# boost.net
KiCad netlist of a schematic drawn in Altium Designer
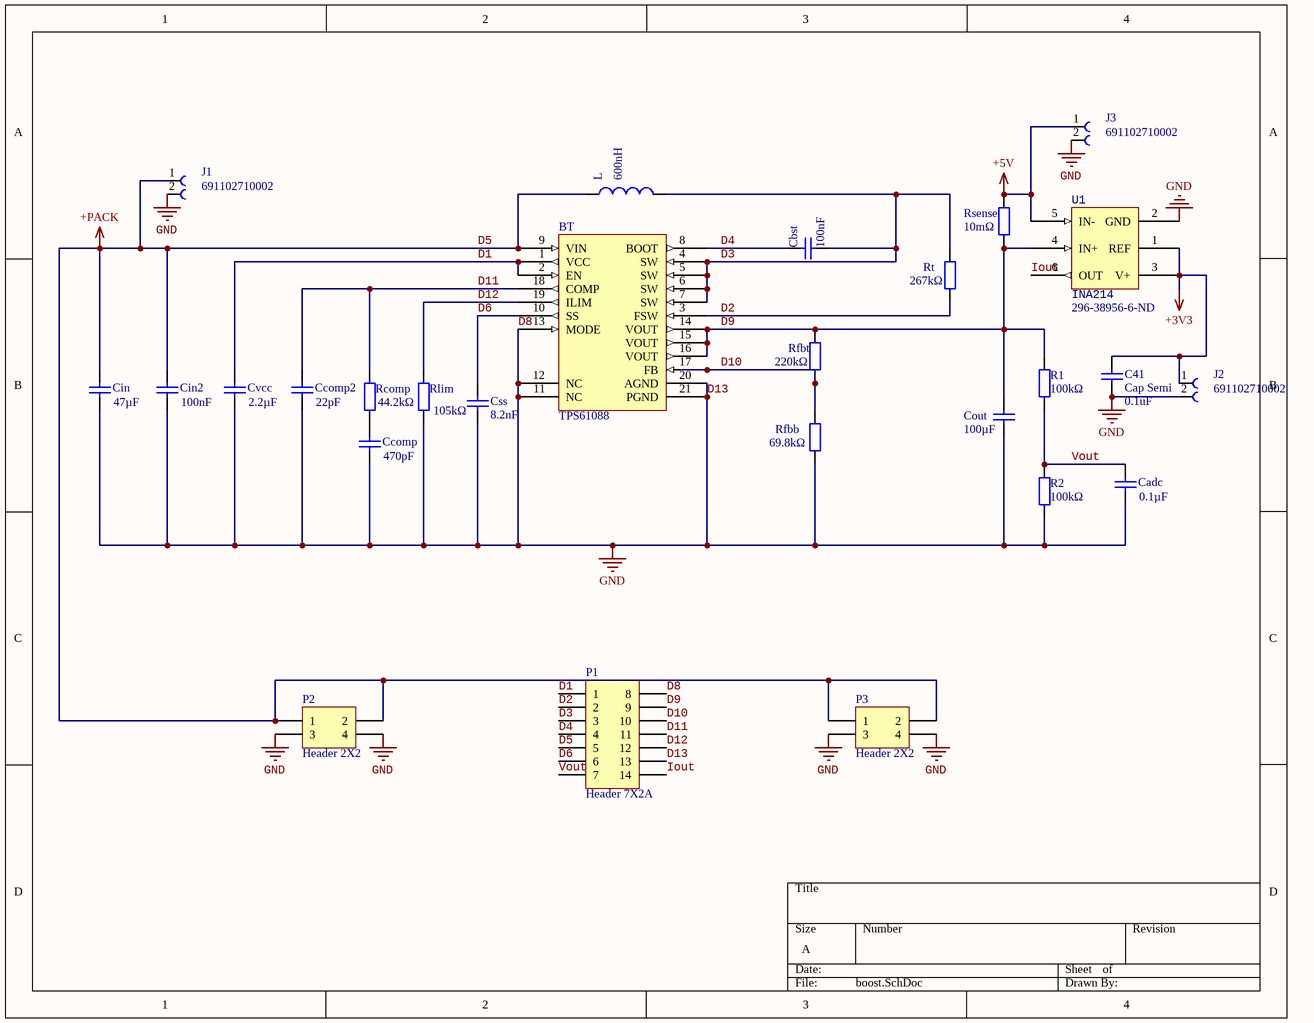
[diagram p0: boost.SchDoc]

(export (version "E")
  (design (tool "Eeschema 10.0.6"))
  (components
    (comp (ref "BT")
      (value "TPS61088")
      (footprint "QFN50P450X350X100-21N")
      (description "Boost converter")
      (libsource (lib "heron-general") (part "TPS61088"))
    )
    (comp (ref "C41")
      (value "Cap Semi")
      (footprint "1608[0603]")
      (description "Capacitor (Semiconductor SIM Model)")
      (fields (field (name "ALTIUM_VALUE") "0.1uF") (field (name "PUBLISHER") "Altium Limited"))
      (libsource (lib "Miscellaneous Devices") (part "Cap Semi"))
    )
    (comp (ref "Cadc")
      (value "0.1µF")
      (footprint "1608[0603]")
      (description "Capacitor")
      (fields (field (name "PUBLISHER") "Altium Limited"))
      (libsource (lib "Miscellaneous Devices") (part "Cap"))
    )
    (comp (ref "Cbst")
      (value "100nF")
      (footprint "1608[0603]")
      (description "Capacitor")
      (fields (field (name "PUBLISHER") "Altium Limited"))
      (libsource (lib "Miscellaneous Devices") (part "Cap"))
    )
    (comp (ref "Ccomp")
      (value "470pF")
      (footprint "1608[0603]")
      (description "Capacitor")
      (fields (field (name "PUBLISHER") "Altium Limited"))
      (libsource (lib "Miscellaneous Devices") (part "Cap"))
    )
    (comp (ref "Ccomp2")
      (value "22pF")
      (footprint "0805")
      (description "Capacitor")
      (fields (field (name "PUBLISHER") "Altium Limited"))
      (libsource (lib "Miscellaneous Devices") (part "Cap"))
    )
    (comp (ref "Cin")
      (value "47µF")
      (footprint "1608[0603]")
      (description "Capacitor")
      (fields (field (name "PUBLISHER") "Altium Limited"))
      (libsource (lib "Miscellaneous Devices") (part "Cap"))
    )
    (comp (ref "Cin2")
      (value "100nF")
      (footprint "1608[0603]")
      (description "Capacitor")
      (fields (field (name "PUBLISHER") "Altium Limited"))
      (libsource (lib "Miscellaneous Devices") (part "Cap"))
    )
    (comp (ref "Cout")
      (value "100µF")
      (footprint "1210")
      (description "Capacitor")
      (fields (field (name "PUBLISHER") "Altium Limited"))
      (libsource (lib "Miscellaneous Devices") (part "Cap"))
    )
    (comp (ref "Css")
      (value "8.2nF")
      (footprint "0805")
      (description "Capacitor")
      (fields (field (name "PUBLISHER") "Altium Limited"))
      (libsource (lib "Miscellaneous Devices") (part "Cap"))
    )
    (comp (ref "Cvcc")
      (value "2.2µF")
      (footprint "0805")
      (description "Capacitor")
      (fields (field (name "PUBLISHER") "Altium Limited"))
      (libsource (lib "Miscellaneous Devices") (part "Cap"))
    )
    (comp (ref "J1")
      (value "691102710002")
      (footprint "691102710002:691102710002")
      (description "102 Series 5mm Pitch Straight, PCB Terminal Block, Through Hole, 2 Way")
      (fields (field (name "MF") "Wurth Electronics"))
      (libsource (lib "691102710002") (part "691102710002"))
    )
    (comp (ref "J2")
      (value "691102710002")
      (footprint "691102710002:691102710002")
      (description "102 Series 5mm Pitch Straight, PCB Terminal Block, Through Hole, 2 Way")
      (fields (field (name "MF") "Wurth Electronics"))
      (libsource (lib "691102710002") (part "691102710002"))
    )
    (comp (ref "J3")
      (value "691102710002")
      (footprint "691102710002:691102710002")
      (description "102 Series 5mm Pitch Straight, PCB Terminal Block, Through Hole, 2 Way")
      (fields (field (name "MF") "Wurth Electronics"))
      (libsource (lib "691102710002") (part "691102710002"))
    )
    (comp (ref "L")
      (value "600nH")
      (footprint "2-SMD")
      (description "Inductor")
      (fields (field (name "PUBLISHER") "Altium Limited"))
      (libsource (lib "Miscellaneous Devices") (part "Inductor"))
    )
    (comp (ref "P1")
      (value "Header 7X2A")
      (footprint "HDR2X7_CEN")
      (description "Header, 7-Pin, Dual row")
      (fields (field (name "PUBLISHER") "Altium Limited"))
      (libsource (lib "Miscellaneous Connectors") (part "Header 7X2A"))
    )
    (comp (ref "P2")
      (value "Header 2X2")
      (footprint "HDR2X2")
      (description "Header, 2-Pin, Dual row")
      (fields (field (name "PUBLISHER") "Altium Limited"))
      (libsource (lib "Miscellaneous Connectors") (part "Header 2X2"))
    )
    (comp (ref "P3")
      (value "Header 2X2")
      (footprint "HDR2X2")
      (description "Header, 2-Pin, Dual row")
      (fields (field (name "PUBLISHER") "Altium Limited"))
      (libsource (lib "Miscellaneous Connectors") (part "Header 2X2"))
    )
    (comp (ref "R1")
      (value "100kΩ")
      (footprint "1608[0603]")
      (description "Resistor")
      (fields (field (name "PUBLISHER") "Altium Limited"))
      (libsource (lib "Miscellaneous Devices") (part "Res2"))
    )
    (comp (ref "R2")
      (value "100kΩ")
      (footprint "1608[0603]")
      (description "Resistor")
      (fields (field (name "PUBLISHER") "Altium Limited"))
      (libsource (lib "Miscellaneous Devices") (part "Res2"))
    )
    (comp (ref "Rcomp")
      (value "44.2kΩ")
      (footprint "0805")
      (description "Resistor")
      (fields (field (name "PUBLISHER") "Altium Limited"))
      (libsource (lib "Miscellaneous Devices") (part "Res2"))
    )
    (comp (ref "Rfbb")
      (value "69.8kΩ")
      (footprint "0805")
      (description "Resistor")
      (fields (field (name "PUBLISHER") "Altium Limited"))
      (libsource (lib "Miscellaneous Devices") (part "Res2"))
    )
    (comp (ref "Rfbt")
      (value "220kΩ")
      (footprint "0805")
      (description "Resistor")
      (fields (field (name "PUBLISHER") "Altium Limited"))
      (libsource (lib "Miscellaneous Devices") (part "Res2"))
    )
    (comp (ref "Rlim")
      (value "105kΩ")
      (footprint "1608[0603]")
      (description "Resistor")
      (fields (field (name "PUBLISHER") "Altium Limited"))
      (libsource (lib "Miscellaneous Devices") (part "Res2"))
    )
    (comp (ref "Rsense")
      (value "10mΩ")
      (footprint "1608[0603]")
      (description "Resistor")
      (fields (field (name "PUBLISHER") "Altium Limited"))
      (libsource (lib "Miscellaneous Devices") (part "Res2"))
    )
    (comp (ref "Rt")
      (value "267kΩ")
      (footprint "1608[0603]")
      (description "Resistor")
      (fields (field (name "Comment") "RtA1") (field (name "PUBLISHER") "Altium Limited"))
      (libsource (lib "") (part "Res2_1"))
    )
    (comp (ref "U1")
      (value "INA214")
      (footprint "SOT65P210X110-6N")
      (description "Current monitor")
      (fields (field (name "SUPPLIER PART NUMBER 1") "296-38956-6-ND"))
      (libsource (lib "heron-general") (part "INA214"))
    )
  )
  (nets
    (net (code "1") (name "+3V3") (class "Default")
      (node (ref "C41") (pin "2") (pinfunction "2_2") (pintype "passive"))
      (node (ref "J2") (pin "1") (pinfunction "1_1") (pintype "passive"))
      (node (ref "U1") (pin "1") (pinfunction "REF_1") (pintype "passive"))
      (node (ref "U1") (pin "3") (pinfunction "V+_3") (pintype "power_in"))
    )
    (net (code "2") (name "+5V") (class "Default")
      (node (ref "J3") (pin "1") (pinfunction "1_1") (pintype "passive"))
      (node (ref "Rsense") (pin "2") (pinfunction "2_2") (pintype "passive"))
      (node (ref "U1") (pin "5") (pinfunction "IN-_5") (pintype "input"))
    )
    (net (code "3") (name "+PACK") (class "Default")
      (node (ref "BT") (pin "9") (pinfunction "VIN_9") (pintype "input"))
      (node (ref "Cin") (pin "2") (pinfunction "2_2") (pintype "passive"))
      (node (ref "Cin2") (pin "2") (pinfunction "2_2") (pintype "passive"))
      (node (ref "J1") (pin "1") (pinfunction "1_1") (pintype "passive"))
      (node (ref "L") (pin "1") (pinfunction "1_1") (pintype "passive"))
      (node (ref "P1") (pin "5") (pinfunction "5_5") (pintype "passive"))
      (node (ref "P2") (pin "1") (pinfunction "1_1") (pintype "passive"))
      (node (ref "P2") (pin "2") (pinfunction "2_2") (pintype "passive"))
      (node (ref "P3") (pin "1") (pinfunction "1_1") (pintype "passive"))
      (node (ref "P3") (pin "2") (pinfunction "2_2") (pintype "passive"))
    )
    (net (code "4") (name "/D1") (class "Default")
      (node (ref "BT") (pin "1") (pinfunction "VCC_1") (pintype "output"))
      (node (ref "BT") (pin "2") (pinfunction "EN_2") (pintype "input"))
      (node (ref "Cvcc") (pin "2") (pinfunction "2_2") (pintype "passive"))
      (node (ref "P1") (pin "1") (pinfunction "1_1") (pintype "passive"))
    )
    (net (code "5") (name "/D2") (class "Default")
      (node (ref "BT") (pin "3") (pinfunction "FSW_3") (pintype "input"))
      (node (ref "P1") (pin "2") (pinfunction "2_2") (pintype "passive"))
      (node (ref "Rt") (pin "2") (pinfunction "2_2") (pintype "passive"))
    )
    (net (code "6") (name "/D3") (class "Default")
      (node (ref "BT") (pin "4") (pinfunction "SW_4") (pintype "input"))
      (node (ref "BT") (pin "5") (pinfunction "SW_5") (pintype "input"))
      (node (ref "BT") (pin "6") (pinfunction "SW_6") (pintype "input"))
      (node (ref "BT") (pin "7") (pinfunction "SW_7") (pintype "input"))
      (node (ref "Cbst") (pin "1") (pinfunction "1_1") (pintype "passive"))
      (node (ref "L") (pin "2") (pinfunction "2_2") (pintype "passive"))
      (node (ref "P1") (pin "3") (pinfunction "3_3") (pintype "passive"))
      (node (ref "Rt") (pin "1") (pinfunction "1_1") (pintype "passive"))
    )
    (net (code "7") (name "/D4") (class "Default")
      (node (ref "BT") (pin "8") (pinfunction "BOOT_8") (pintype "output"))
      (node (ref "Cbst") (pin "2") (pinfunction "2_2") (pintype "passive"))
      (node (ref "P1") (pin "4") (pinfunction "4_4") (pintype "passive"))
    )
    (net (code "8") (name "/D6") (class "Default")
      (node (ref "BT") (pin "10") (pinfunction "SS_10") (pintype "output"))
      (node (ref "Css") (pin "2") (pinfunction "2_2") (pintype "passive"))
      (node (ref "P1") (pin "6") (pinfunction "6_6") (pintype "passive"))
    )
    (net (code "9") (name "/D9") (class "Default")
      (node (ref "BT") (pin "14") (pinfunction "VOUT_14") (pintype "output"))
      (node (ref "BT") (pin "15") (pinfunction "VOUT_15") (pintype "output"))
      (node (ref "BT") (pin "16") (pinfunction "VOUT_16") (pintype "output"))
      (node (ref "Cout") (pin "2") (pinfunction "2_2") (pintype "passive"))
      (node (ref "P1") (pin "9") (pinfunction "9_9") (pintype "passive"))
      (node (ref "R1") (pin "2") (pinfunction "2_2") (pintype "passive"))
      (node (ref "Rfbt") (pin "2") (pinfunction "2_2") (pintype "passive"))
      (node (ref "Rsense") (pin "1") (pinfunction "1_1") (pintype "passive"))
      (node (ref "U1") (pin "4") (pinfunction "IN+_4") (pintype "input"))
    )
    (net (code "10") (name "/D10") (class "Default")
      (node (ref "BT") (pin "17") (pinfunction "FB_17") (pintype "input"))
      (node (ref "P1") (pin "10") (pinfunction "10_10") (pintype "passive"))
      (node (ref "Rfbb") (pin "2") (pinfunction "2_2") (pintype "passive"))
      (node (ref "Rfbt") (pin "1") (pinfunction "1_1") (pintype "passive"))
    )
    (net (code "11") (name "/D11") (class "Default")
      (node (ref "BT") (pin "18") (pinfunction "COMP_18") (pintype "output"))
      (node (ref "Ccomp2") (pin "2") (pinfunction "2_2") (pintype "passive"))
      (node (ref "P1") (pin "11") (pinfunction "11_11") (pintype "passive"))
      (node (ref "Rcomp") (pin "2") (pinfunction "2_2") (pintype "passive"))
    )
    (net (code "12") (name "/D12") (class "Default")
      (node (ref "BT") (pin "19") (pinfunction "ILIM_19") (pintype "output"))
      (node (ref "P1") (pin "12") (pinfunction "12_12") (pintype "passive"))
      (node (ref "Rlim") (pin "2") (pinfunction "2_2") (pintype "passive"))
    )
    (net (code "13") (name "/Iout") (class "Default")
      (node (ref "P1") (pin "14") (pinfunction "14_14") (pintype "passive"))
      (node (ref "U1") (pin "6") (pinfunction "OUT_6") (pintype "output"))
    )
    (net (code "14") (name "/Vout") (class "Default")
      (node (ref "Cadc") (pin "1") (pinfunction "1_1") (pintype "passive"))
      (node (ref "P1") (pin "7") (pinfunction "7_7") (pintype "passive"))
      (node (ref "R1") (pin "1") (pinfunction "1_1") (pintype "passive"))
      (node (ref "R2") (pin "2") (pinfunction "2_2") (pintype "passive"))
    )
    (net (code "15") (name "GND") (class "Default")
      (node (ref "BT") (pin "11") (pinfunction "NC_11") (pintype "passive"))
      (node (ref "BT") (pin "12") (pinfunction "NC_12") (pintype "passive"))
      (node (ref "BT") (pin "13") (pinfunction "MODE_13") (pintype "input"))
      (node (ref "BT") (pin "20") (pinfunction "AGND_20") (pintype "power_in"))
      (node (ref "BT") (pin "21") (pinfunction "PGND_21") (pintype "power_in"))
      (node (ref "C41") (pin "1") (pinfunction "1_1") (pintype "passive"))
      (node (ref "Cadc") (pin "2") (pinfunction "2_2") (pintype "passive"))
      (node (ref "Ccomp") (pin "1") (pinfunction "1_1") (pintype "passive"))
      (node (ref "Ccomp2") (pin "1") (pinfunction "1_1") (pintype "passive"))
      (node (ref "Cin") (pin "1") (pinfunction "1_1") (pintype "passive"))
      (node (ref "Cin2") (pin "1") (pinfunction "1_1") (pintype "passive"))
      (node (ref "Cout") (pin "1") (pinfunction "1_1") (pintype "passive"))
      (node (ref "Css") (pin "1") (pinfunction "1_1") (pintype "passive"))
      (node (ref "Cvcc") (pin "1") (pinfunction "1_1") (pintype "passive"))
      (node (ref "J1") (pin "2") (pinfunction "2_2") (pintype "passive"))
      (node (ref "J2") (pin "2") (pinfunction "2_2") (pintype "passive"))
      (node (ref "J3") (pin "2") (pinfunction "2_2") (pintype "passive"))
      (node (ref "P1") (pin "13") (pinfunction "13_13") (pintype "passive"))
      (node (ref "P1") (pin "8") (pinfunction "8_8") (pintype "passive"))
      (node (ref "P2") (pin "3") (pinfunction "3_3") (pintype "passive"))
      (node (ref "P2") (pin "4") (pinfunction "4_4") (pintype "passive"))
      (node (ref "P3") (pin "3") (pinfunction "3_3") (pintype "passive"))
      (node (ref "P3") (pin "4") (pinfunction "4_4") (pintype "passive"))
      (node (ref "R2") (pin "1") (pinfunction "1_1") (pintype "passive"))
      (node (ref "Rfbb") (pin "1") (pinfunction "1_1") (pintype "passive"))
      (node (ref "Rlim") (pin "1") (pinfunction "1_1") (pintype "passive"))
      (node (ref "U1") (pin "2") (pinfunction "GND_2") (pintype "power_in"))
    )
    (net (code "16") (name "Net-(Ccomp-Pad2)") (class "Default")
      (node (ref "Ccomp") (pin "2") (pinfunction "2_2") (pintype "passive"))
      (node (ref "Rcomp") (pin "1") (pinfunction "1_1") (pintype "passive"))
    )
  )
)
